# top.net
KiCad netlist of a schematic drawn in EAGLE
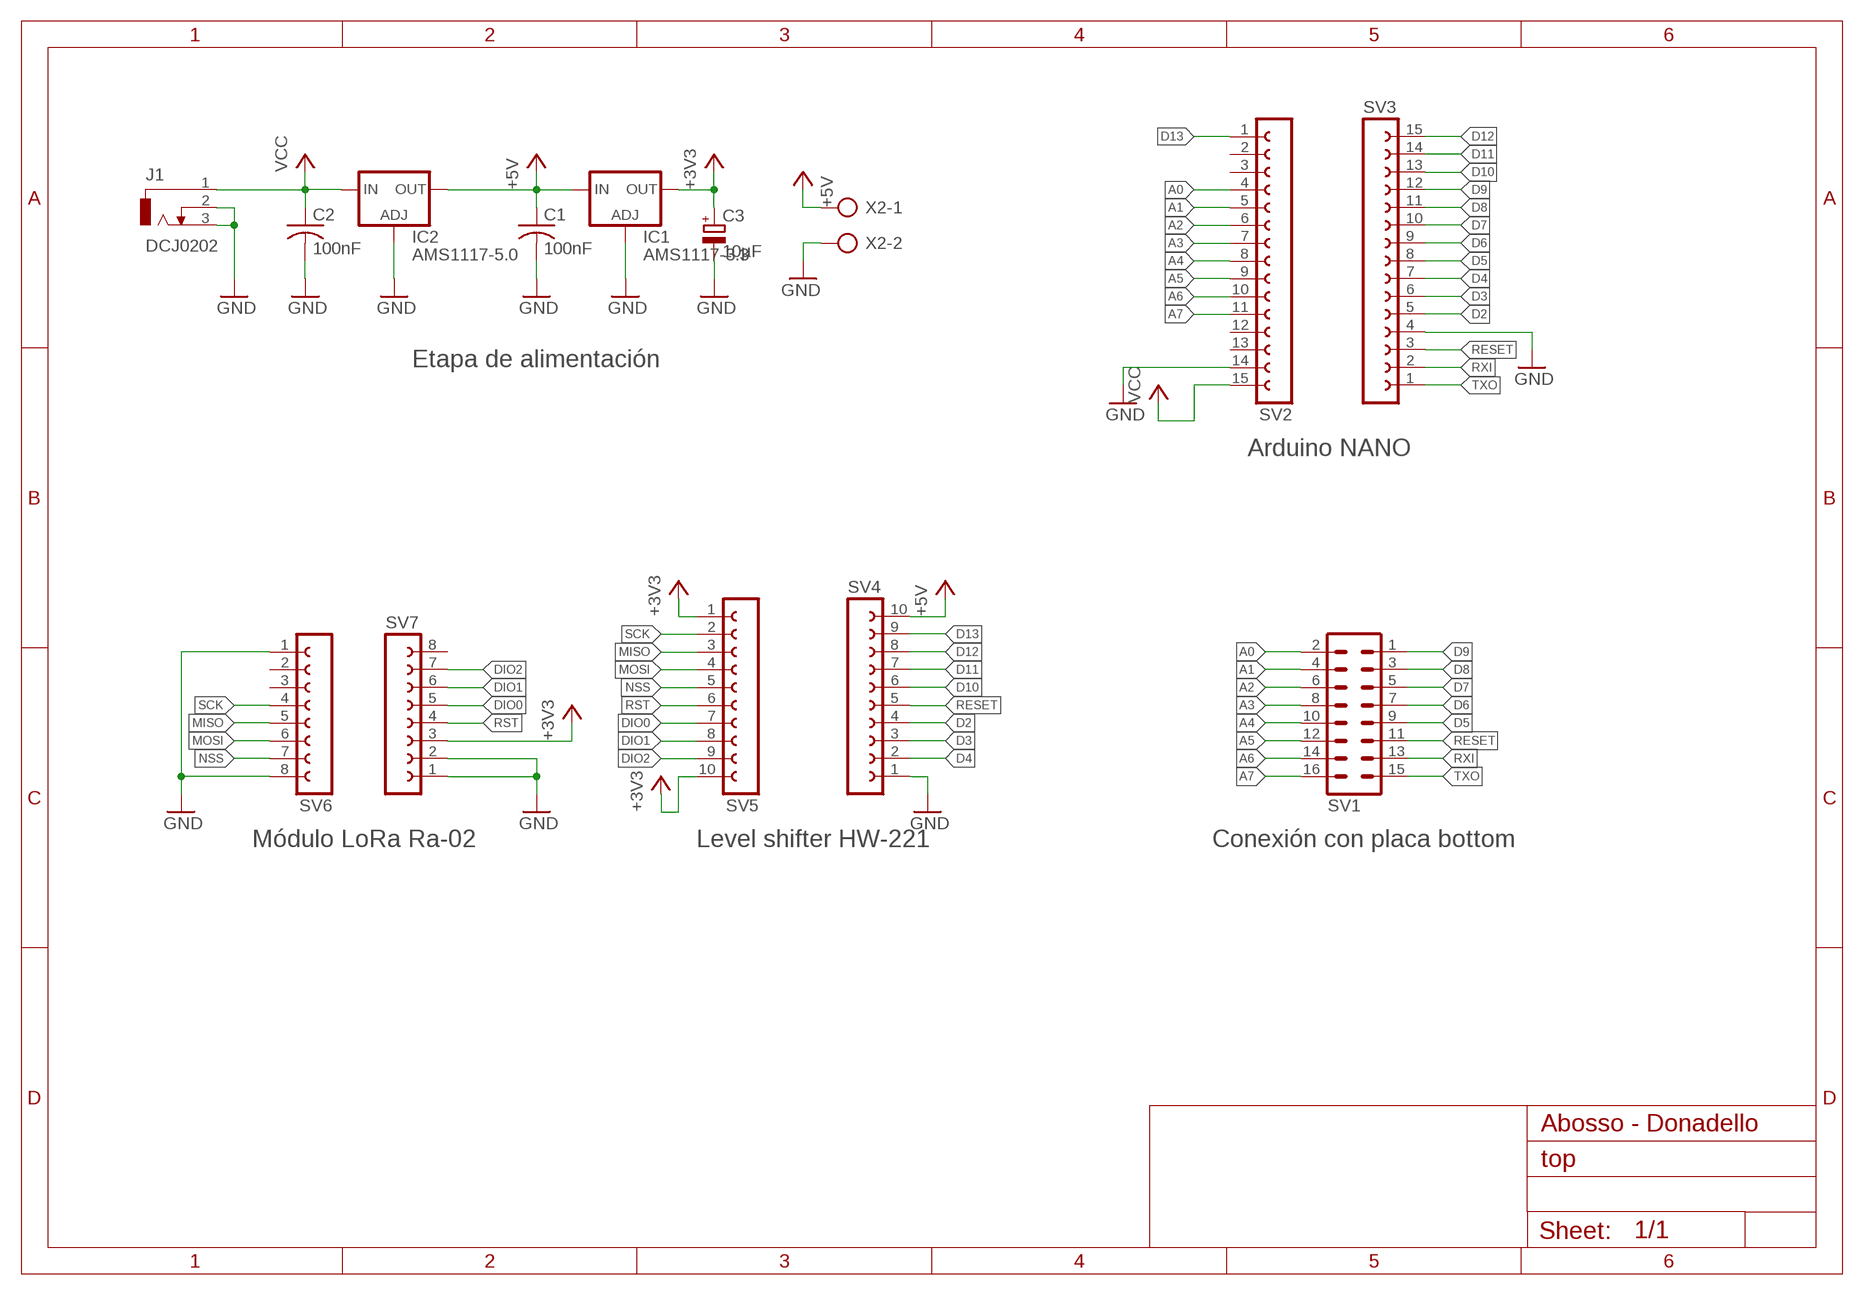
[diagram p0: schematic, sheet 1]

(export (version "E")
  (design (tool "Eeschema 10.0.6"))
  (components
    (comp (ref "C1")
      (value "100nF")
      (footprint "eagle-import:C0805")
      (libsource (lib "eagle-import") (part "C-USC0805"))
    )
    (comp (ref "C2")
      (value "100nF")
      (footprint "eagle-import:C0805")
      (libsource (lib "eagle-import") (part "C-USC0805"))
    )
    (comp (ref "C3")
      (value "10µF")
      (footprint "eagle-import:PANASONIC_B")
      (libsource (lib "eagle-import") (part "CPOL-EUB"))
    )
    (comp (ref "IC1")
      (value "AMS1117-3.3")
      (footprint "eagle-import:SOT223")
      (libsource (lib "eagle-import") (part "LD117A?S33TR"))
    )
    (comp (ref "IC2")
      (value "AMS1117-5.0")
      (footprint "eagle-import:SOT223")
      (libsource (lib "eagle-import") (part "LD117A?S50TR"))
    )
    (comp (ref "J1")
      (value "DCJ0202")
      (footprint "eagle-import:DCJ0202")
      (libsource (lib "eagle-import") (part "DCJ0202"))
    )
    (comp (ref "SV1")
      (value "MA08-2")
      (footprint "eagle-import:MA08-2")
      (libsource (lib "eagle-import") (part "MA08-2"))
    )
    (comp (ref "SV2")
      (value "FE15-1")
      (footprint "eagle-import:FE15")
      (libsource (lib "eagle-import") (part "FE15-1"))
    )
    (comp (ref "SV3")
      (value "FE15-1")
      (footprint "eagle-import:FE15")
      (libsource (lib "eagle-import") (part "FE15-1"))
    )
    (comp (ref "SV4")
      (value "FE10-1")
      (footprint "eagle-import:FE10")
      (libsource (lib "eagle-import") (part "FE10-1"))
    )
    (comp (ref "SV5")
      (value "FE10-1")
      (footprint "eagle-import:FE10")
      (libsource (lib "eagle-import") (part "FE10-1"))
    )
    (comp (ref "SV6")
      (value "FE08-1")
      (footprint "eagle-import:FE08")
      (libsource (lib "eagle-import") (part "FE08-1"))
    )
    (comp (ref "SV7")
      (value "FE08-1")
      (footprint "eagle-import:FE08")
      (libsource (lib "eagle-import") (part "FE08-1"))
    )
    (comp (ref "X2")
      (value "AK500/2")
      (footprint "eagle-import:AK500_2")
      (libsource (lib "eagle-import") (part "AK500/2"))
    )
  )
  (nets
    (net (code "1") (name "+3V3") (class "Default")
      (node (ref "C3") (pin "+") (pinfunction "+_+") (pintype "passive"))
      (node (ref "IC1") (pin "4") (pinfunction "OUT_4") (pintype "passive"))
      (node (ref "SV5") (pin "1") (pinfunction "1_1") (pintype "passive"))
      (node (ref "SV5") (pin "10") (pinfunction "10_10") (pintype "passive"))
      (node (ref "SV7") (pin "3") (pinfunction "3_3") (pintype "passive"))
    )
    (net (code "2") (name "+5V") (class "Default")
      (node (ref "C1") (pin "1") (pinfunction "1_1") (pintype "passive"))
      (node (ref "IC1") (pin "3") (pinfunction "IN_3") (pintype "input"))
      (node (ref "IC2") (pin "4") (pinfunction "OUT_4") (pintype "passive"))
      (node (ref "SV4") (pin "10") (pinfunction "10_10") (pintype "passive"))
      (node (ref "X2") (pin "1") (pinfunction "KL_1") (pintype "passive"))
    )
    (net (code "3") (name "A0") (class "Default")
      (node (ref "SV1") (pin "2") (pinfunction "2_2") (pintype "passive"))
      (node (ref "SV2") (pin "4") (pinfunction "4_4") (pintype "passive"))
    )
    (net (code "4") (name "A1") (class "Default")
      (node (ref "SV1") (pin "4") (pinfunction "4_4") (pintype "passive"))
      (node (ref "SV2") (pin "5") (pinfunction "5_5") (pintype "passive"))
    )
    (net (code "5") (name "A2") (class "Default")
      (node (ref "SV1") (pin "6") (pinfunction "6_6") (pintype "passive"))
      (node (ref "SV2") (pin "6") (pinfunction "6_6") (pintype "passive"))
    )
    (net (code "6") (name "A3") (class "Default")
      (node (ref "SV1") (pin "8") (pinfunction "8_8") (pintype "passive"))
      (node (ref "SV2") (pin "7") (pinfunction "7_7") (pintype "passive"))
    )
    (net (code "7") (name "A4") (class "Default")
      (node (ref "SV1") (pin "10") (pinfunction "10_10") (pintype "passive"))
      (node (ref "SV2") (pin "8") (pinfunction "8_8") (pintype "passive"))
    )
    (net (code "8") (name "A5") (class "Default")
      (node (ref "SV1") (pin "12") (pinfunction "12_12") (pintype "passive"))
      (node (ref "SV2") (pin "9") (pinfunction "9_9") (pintype "passive"))
    )
    (net (code "9") (name "A6") (class "Default")
      (node (ref "SV1") (pin "14") (pinfunction "14_14") (pintype "passive"))
      (node (ref "SV2") (pin "10") (pinfunction "10_10") (pintype "passive"))
    )
    (net (code "10") (name "A7") (class "Default")
      (node (ref "SV1") (pin "16") (pinfunction "16_16") (pintype "passive"))
      (node (ref "SV2") (pin "11") (pinfunction "11_11") (pintype "passive"))
    )
    (net (code "11") (name "D2") (class "Default")
      (node (ref "SV3") (pin "5") (pinfunction "5_5") (pintype "passive"))
      (node (ref "SV4") (pin "4") (pinfunction "4_4") (pintype "passive"))
    )
    (net (code "12") (name "D3") (class "Default")
      (node (ref "SV3") (pin "6") (pinfunction "6_6") (pintype "passive"))
      (node (ref "SV4") (pin "3") (pinfunction "3_3") (pintype "passive"))
    )
    (net (code "13") (name "D4") (class "Default")
      (node (ref "SV3") (pin "7") (pinfunction "7_7") (pintype "passive"))
      (node (ref "SV4") (pin "2") (pinfunction "2_2") (pintype "passive"))
    )
    (net (code "14") (name "D5") (class "Default")
      (node (ref "SV1") (pin "9") (pinfunction "9_9") (pintype "passive"))
      (node (ref "SV3") (pin "8") (pinfunction "8_8") (pintype "passive"))
    )
    (net (code "15") (name "D6") (class "Default")
      (node (ref "SV1") (pin "7") (pinfunction "7_7") (pintype "passive"))
      (node (ref "SV3") (pin "9") (pinfunction "9_9") (pintype "passive"))
    )
    (net (code "16") (name "D7") (class "Default")
      (node (ref "SV1") (pin "5") (pinfunction "5_5") (pintype "passive"))
      (node (ref "SV3") (pin "10") (pinfunction "10_10") (pintype "passive"))
    )
    (net (code "17") (name "D8") (class "Default")
      (node (ref "SV1") (pin "3") (pinfunction "3_3") (pintype "passive"))
      (node (ref "SV3") (pin "11") (pinfunction "11_11") (pintype "passive"))
    )
    (net (code "18") (name "D9") (class "Default")
      (node (ref "SV1") (pin "1") (pinfunction "1_1") (pintype "passive"))
      (node (ref "SV3") (pin "12") (pinfunction "12_12") (pintype "passive"))
    )
    (net (code "19") (name "D10") (class "Default")
      (node (ref "SV3") (pin "13") (pinfunction "13_13") (pintype "passive"))
      (node (ref "SV4") (pin "6") (pinfunction "6_6") (pintype "passive"))
    )
    (net (code "20") (name "D11") (class "Default")
      (node (ref "SV3") (pin "14") (pinfunction "14_14") (pintype "passive"))
      (node (ref "SV4") (pin "7") (pinfunction "7_7") (pintype "passive"))
    )
    (net (code "21") (name "D12") (class "Default")
      (node (ref "SV3") (pin "15") (pinfunction "15_15") (pintype "passive"))
      (node (ref "SV4") (pin "8") (pinfunction "8_8") (pintype "passive"))
    )
    (net (code "22") (name "D13") (class "Default")
      (node (ref "SV2") (pin "1") (pinfunction "1_1") (pintype "passive"))
      (node (ref "SV4") (pin "9") (pinfunction "9_9") (pintype "passive"))
    )
    (net (code "23") (name "DIO0") (class "Default")
      (node (ref "SV5") (pin "7") (pinfunction "7_7") (pintype "passive"))
      (node (ref "SV7") (pin "5") (pinfunction "5_5") (pintype "passive"))
    )
    (net (code "24") (name "DIO1") (class "Default")
      (node (ref "SV5") (pin "8") (pinfunction "8_8") (pintype "passive"))
      (node (ref "SV7") (pin "6") (pinfunction "6_6") (pintype "passive"))
    )
    (net (code "25") (name "DIO2") (class "Default")
      (node (ref "SV5") (pin "9") (pinfunction "9_9") (pintype "passive"))
      (node (ref "SV7") (pin "7") (pinfunction "7_7") (pintype "passive"))
    )
    (net (code "26") (name "GND") (class "Default")
      (node (ref "C1") (pin "2") (pinfunction "2_2") (pintype "passive"))
      (node (ref "C2") (pin "2") (pinfunction "2_2") (pintype "passive"))
      (node (ref "C3") (pin "-") (pinfunction "-_-") (pintype "passive"))
      (node (ref "IC1") (pin "1") (pinfunction "ADJ_1") (pintype "input"))
      (node (ref "IC2") (pin "1") (pinfunction "ADJ_1") (pintype "input"))
      (node (ref "J1") (pin "2") (pinfunction "2_2") (pintype "passive"))
      (node (ref "J1") (pin "3") (pinfunction "3_3") (pintype "passive"))
      (node (ref "SV2") (pin "14") (pinfunction "14_14") (pintype "passive"))
      (node (ref "SV3") (pin "4") (pinfunction "4_4") (pintype "passive"))
      (node (ref "SV4") (pin "1") (pinfunction "1_1") (pintype "passive"))
      (node (ref "SV6") (pin "1") (pinfunction "1_1") (pintype "passive"))
      (node (ref "SV6") (pin "8") (pinfunction "8_8") (pintype "passive"))
      (node (ref "SV7") (pin "1") (pinfunction "1_1") (pintype "passive"))
      (node (ref "SV7") (pin "2") (pinfunction "2_2") (pintype "passive"))
      (node (ref "X2") (pin "2") (pinfunction "KL_2") (pintype "passive"))
    )
    (net (code "27") (name "MISO") (class "Default")
      (node (ref "SV5") (pin "3") (pinfunction "3_3") (pintype "passive"))
      (node (ref "SV6") (pin "5") (pinfunction "5_5") (pintype "passive"))
    )
    (net (code "28") (name "MOSI") (class "Default")
      (node (ref "SV5") (pin "4") (pinfunction "4_4") (pintype "passive"))
      (node (ref "SV6") (pin "6") (pinfunction "6_6") (pintype "passive"))
    )
    (net (code "29") (name "NSS") (class "Default")
      (node (ref "SV5") (pin "5") (pinfunction "5_5") (pintype "passive"))
      (node (ref "SV6") (pin "7") (pinfunction "7_7") (pintype "passive"))
    )
    (net (code "30") (name "RESET") (class "Default")
      (node (ref "SV1") (pin "11") (pinfunction "11_11") (pintype "passive"))
      (node (ref "SV3") (pin "3") (pinfunction "3_3") (pintype "passive"))
      (node (ref "SV4") (pin "5") (pinfunction "5_5") (pintype "passive"))
    )
    (net (code "31") (name "RST") (class "Default")
      (node (ref "SV5") (pin "6") (pinfunction "6_6") (pintype "passive"))
      (node (ref "SV7") (pin "4") (pinfunction "4_4") (pintype "passive"))
    )
    (net (code "32") (name "RXI") (class "Default")
      (node (ref "SV1") (pin "13") (pinfunction "13_13") (pintype "passive"))
      (node (ref "SV3") (pin "2") (pinfunction "2_2") (pintype "passive"))
    )
    (net (code "33") (name "SCK") (class "Default")
      (node (ref "SV5") (pin "2") (pinfunction "2_2") (pintype "passive"))
      (node (ref "SV6") (pin "4") (pinfunction "4_4") (pintype "passive"))
    )
    (net (code "34") (name "TXO") (class "Default")
      (node (ref "SV1") (pin "15") (pinfunction "15_15") (pintype "passive"))
      (node (ref "SV3") (pin "1") (pinfunction "1_1") (pintype "passive"))
    )
    (net (code "35") (name "VCC") (class "Default")
      (node (ref "C2") (pin "1") (pinfunction "1_1") (pintype "passive"))
      (node (ref "IC2") (pin "3") (pinfunction "IN_3") (pintype "input"))
      (node (ref "J1") (pin "1") (pinfunction "1_1") (pintype "passive"))
      (node (ref "SV2") (pin "15") (pinfunction "15_15") (pintype "passive"))
    )
    (net (code "36") (name "unconnected-(SV2-Pad2)") (class "Default")
      (node (ref "SV2") (pin "2") (pinfunction "2_2") (pintype "passive"))
    )
    (net (code "37") (name "unconnected-(SV2-Pad3)") (class "Default")
      (node (ref "SV2") (pin "3") (pinfunction "3_3") (pintype "passive"))
    )
    (net (code "38") (name "unconnected-(SV2-Pad12)") (class "Default")
      (node (ref "SV2") (pin "12") (pinfunction "12_12") (pintype "passive"))
    )
    (net (code "39") (name "unconnected-(SV2-Pad13)") (class "Default")
      (node (ref "SV2") (pin "13") (pinfunction "13_13") (pintype "passive"))
    )
    (net (code "40") (name "unconnected-(SV6-Pad2)") (class "Default")
      (node (ref "SV6") (pin "2") (pinfunction "2_2") (pintype "passive"))
    )
    (net (code "41") (name "unconnected-(SV6-Pad3)") (class "Default")
      (node (ref "SV6") (pin "3") (pinfunction "3_3") (pintype "passive"))
    )
    (net (code "42") (name "unconnected-(SV7-Pad8)") (class "Default")
      (node (ref "SV7") (pin "8") (pinfunction "8_8") (pintype "passive"))
    )
  )
)
